# GPS.net
KiCad netlist of a schematic drawn in Altium Designer
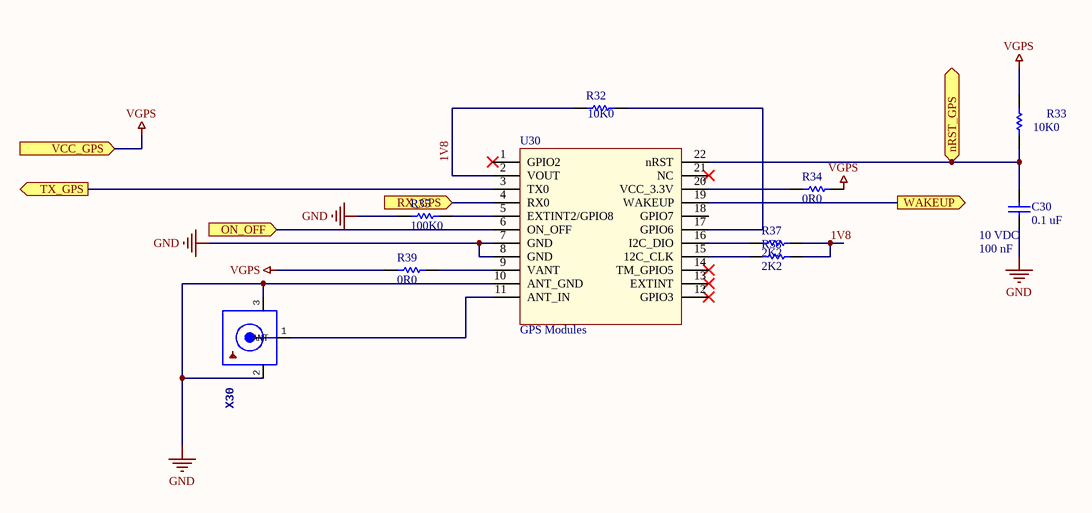
[diagram p0: GPS.SchDoc]

(export (version "E")
  (design (tool "Eeschema 10.0.6"))
  (components
    (comp (ref "C30")
      (value "100 nF, 10 V")
      (footprint "C0402")
      (description "Multilayer Ceramic Capacitors MLCC - SMD/SMT 0402 0.1uF 10volts X7R 10%")
      (fields
        (field (name "MANUFACTURER") "Murata Electronics")
        (field (name "MANUFACTURER PART NUMBER") "GRM155R71A104KA01D")
        (field (name "CAPACITANCE") "0.1 uF")
        (field (name "VOLTAGE RATING DC") "10 VDC")
        (field (name "CAPACITANCE - NF") "100 nF")
      )
      (libsource (lib "PULV3") (part "100 nF, 10 V"))
    )
    (comp (ref "R32")
      (value "10K0")
      (footprint "0402_RES")
      (description "Resistor")
      (fields (field (name "MANUFACTURER PART NUMBER") "CRCW040210K0FKTD"))
      (libsource (lib "PULV3") (part "10 KOHM, 63 mW"))
    )
    (comp (ref "R33")
      (value "10K0")
      (footprint "0402_RES")
      (description "Resistor")
      (fields (field (name "MANUFACTURER PART NUMBER") "CRCW040210K0FKTD"))
      (libsource (lib "PULV3") (part "10 KOHM, 63 mW"))
    )
    (comp (ref "R34")
      (value "PANASONIC ELECTRONIC COMPONENTS")
      (footprint "0402_RES")
      (description "Resistor")
      (fields (field (name "MANUFACTURER PART NUMBER") "ERJ-2GE0R00X") (field (name "RESISTANCE") "0R0"))
      (libsource (lib "PULV3") (part "0R0"))
    )
    (comp (ref "R35")
      (value "CRCW0402100KFKED")
      (footprint "0402_RES")
      (description "Resistor")
      (fields (field (name "MANUFACTURER") "VISHAY") (field (name "RESISTANCE") "100K0"))
      (libsource (lib "PULV3") (part "100K0,63mW"))
    )
    (comp (ref "R37")
      (value "ERJ-2RKF2201X")
      (footprint "0402_RES")
      (description "Resistor")
      (fields (field (name "MANUFACTURER") "PANASONIC") (field (name "RESISTANCE") "2K2"))
      (libsource (lib "PULV3") (part "2K2"))
    )
    (comp (ref "R38")
      (value "ERJ-2RKF2201X")
      (footprint "0402_RES")
      (description "Resistor")
      (fields (field (name "MANUFACTURER") "PANASONIC") (field (name "RESISTANCE") "2K2"))
      (libsource (lib "PULV3") (part "2K2"))
    )
    (comp (ref "R39")
      (value "PANASONIC ELECTRONIC COMPONENTS")
      (footprint "0402_RES")
      (description "Resistor")
      (fields (field (name "MANUFACTURER PART NUMBER") "ERJ-2GE0R00X") (field (name "RESISTANCE") "0R0"))
      (libsource (lib "PULV3") (part "0R0"))
    )
    (comp (ref "U30")
      (value "927-A2200-A")
      (footprint "GPS")
      (description "GPS")
      (fields
        (field (name "MANUFACTURER") "Maestro Wireless Solutions")
        (field (name "MANUFACTURER PART NUMBER") "A2200-A")
        (field (name "PRODUCT TYPE") "GPS Modules")
      )
      (libsource (lib "PULV3") (part "GPS"))
    )
    (comp (ref "X30")
      (value "RECE.20279.001E.01")
      (footprint "U.FL")
      (description "Connector UFL")
      (fields (field (name "MANUFACTURER") "Taoglas"))
      (libsource (lib "PULV3") (part "SMACONNECTOR_UFL"))
    )
  )
  (nets
    (net (code "1") (name "/1V8") (class "Default")
      (node (ref "R32") (pin "1") (pinfunction "1_1") (pintype "passive"))
      (node (ref "R37") (pin "2") (pinfunction "2_2") (pintype "passive"))
      (node (ref "R38") (pin "2") (pinfunction "2_2") (pintype "passive"))
      (node (ref "U30") (pin "2") (pinfunction "VOUT_2") (pintype "passive"))
    )
    (net (code "2") (name "/ON_OFF") (class "Default")
      (node (ref "U30") (pin "6") (pinfunction "ON_OFF_6") (pintype "passive"))
    )
    (net (code "3") (name "/RX_GPS") (class "Default")
      (node (ref "U30") (pin "4") (pinfunction "RX0_4") (pintype "passive"))
    )
    (net (code "4") (name "/TX_GPS") (class "Default")
      (node (ref "U30") (pin "3") (pinfunction "TX0_3") (pintype "passive"))
    )
    (net (code "5") (name "/WAKEUP") (class "Default")
      (node (ref "U30") (pin "19") (pinfunction "WAKEUP_19") (pintype "passive"))
    )
    (net (code "6") (name "/nRST_GPS") (class "Default")
      (node (ref "C30") (pin "1") (pinfunction "1_1") (pintype "passive"))
      (node (ref "R33") (pin "1") (pinfunction "1_1") (pintype "passive"))
      (node (ref "U30") (pin "22") (pinfunction "nRST_22") (pintype "passive"))
    )
    (net (code "7") (name "GND") (class "Default")
      (node (ref "C30") (pin "2") (pinfunction "2_2") (pintype "passive"))
      (node (ref "R35") (pin "1") (pinfunction "1_1") (pintype "passive"))
      (node (ref "U30") (pin "10") (pinfunction "ANT_GND_10") (pintype "passive"))
      (node (ref "U30") (pin "7") (pinfunction "GND_7") (pintype "passive"))
      (node (ref "U30") (pin "8") (pinfunction "GND_8") (pintype "passive"))
      (node (ref "X30") (pin "2") (pinfunction "GND_2") (pintype "power_in"))
      (node (ref "X30") (pin "3") (pinfunction "GND_3") (pintype "power_in"))
    )
    (net (code "8") (name "Net-(U30-12C_CLK)") (class "Default")
      (node (ref "R38") (pin "1") (pinfunction "1_1") (pintype "passive"))
      (node (ref "U30") (pin "15") (pinfunction "12C_CLK_15") (pintype "passive"))
    )
    (net (code "9") (name "Net-(U30-ANT_IN)") (class "Default")
      (node (ref "U30") (pin "11") (pinfunction "ANT_IN_11") (pintype "passive"))
      (node (ref "X30") (pin "1") (pinfunction "ANT_1") (pintype "passive"))
    )
    (net (code "10") (name "Net-(U30-EXTINT2{slash}GPIO8)") (class "Default")
      (node (ref "R35") (pin "2") (pinfunction "2_2") (pintype "passive"))
      (node (ref "U30") (pin "5") (pinfunction "EXTINT2/GPIO8_5") (pintype "passive"))
    )
    (net (code "11") (name "Net-(U30-GPIO6)") (class "Default")
      (node (ref "R32") (pin "2") (pinfunction "2_2") (pintype "passive"))
      (node (ref "U30") (pin "17") (pinfunction "GPIO6_17") (pintype "passive"))
    )
    (net (code "12") (name "Net-(U30-I2C_DIO)") (class "Default")
      (node (ref "R37") (pin "1") (pinfunction "1_1") (pintype "passive"))
      (node (ref "U30") (pin "16") (pinfunction "I2C_DIO_16") (pintype "passive"))
    )
    (net (code "13") (name "Net-(U30-VANT)") (class "Default")
      (node (ref "R39") (pin "2") (pinfunction "2_2") (pintype "passive"))
      (node (ref "U30") (pin "9") (pinfunction "VANT_9") (pintype "passive"))
    )
    (net (code "14") (name "Net-(U30-VCC_3.3V)") (class "Default")
      (node (ref "R34") (pin "1") (pinfunction "1_1") (pintype "passive"))
      (node (ref "U30") (pin "20") (pinfunction "VCC_3.3V_20") (pintype "passive"))
    )
    (net (code "15") (name "VGPS") (class "Default")
      (node (ref "R33") (pin "2") (pinfunction "2_2") (pintype "passive"))
      (node (ref "R34") (pin "2") (pinfunction "2_2") (pintype "passive"))
      (node (ref "R39") (pin "1") (pinfunction "1_1") (pintype "passive"))
    )
    (net (code "16") (name "unconnected-(U30-EXTINT-Pad13)") (class "Default")
      (node (ref "U30") (pin "13") (pinfunction "EXTINT_13") (pintype "passive+no_connect"))
    )
    (net (code "17") (name "unconnected-(U30-GPIO2-Pad1)") (class "Default")
      (node (ref "U30") (pin "1") (pinfunction "GPIO2_1") (pintype "passive+no_connect"))
    )
    (net (code "18") (name "unconnected-(U30-GPIO3-Pad12)") (class "Default")
      (node (ref "U30") (pin "12") (pinfunction "GPIO3_12") (pintype "passive+no_connect"))
    )
    (net (code "19") (name "unconnected-(U30-GPIO7-Pad18)") (class "Default")
      (node (ref "U30") (pin "18") (pinfunction "GPIO7_18") (pintype "passive"))
    )
    (net (code "20") (name "unconnected-(U30-NC-Pad21)") (class "Default")
      (node (ref "U30") (pin "21") (pinfunction "NC_21") (pintype "passive+no_connect"))
    )
    (net (code "21") (name "unconnected-(U30-TM_GPIO5-Pad14)") (class "Default")
      (node (ref "U30") (pin "14") (pinfunction "TM_GPIO5_14") (pintype "passive+no_connect"))
    )
  )
)
